# OpenMoteSTM-Border_JTAG.net
KiCad netlist of a schematic drawn in Altium Designer
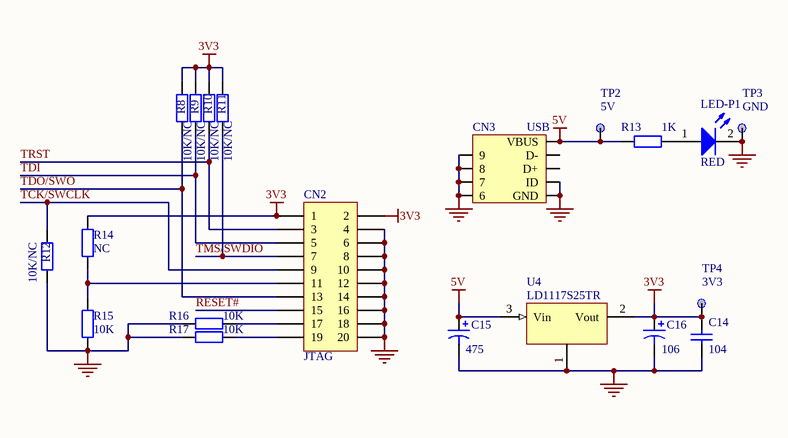
[diagram p0: OpenMoteSTM-Border_JTAG.SchDoc]

(export (version "E")
  (design (tool "Eeschema 10.0.6"))
  (components
    (comp (ref "C14")
      (value "104")
      (footprint "0603")
      (description "Capacitor")
      (fields (field (name "Comment") "Cap") (field (name "PUBLISHER") "Altium Limited"))
      (libsource (lib "Miscellaneous Devices") (part "Cap"))
    )
    (comp (ref "C15")
      (value "475")
      (footprint "1210")
      (description "Polarized Capacitor (Radial)")
      (fields (field (name "Comment") "Cap Pol1") (field (name "PUBLISHER") "Altium Limited"))
      (libsource (lib "Miscellaneous Devices") (part "Cap Pol1"))
    )
    (comp (ref "C16")
      (value "106")
      (footprint "1210")
      (description "Polarized Capacitor (Radial)")
      (fields (field (name "Comment") "Cap Pol1") (field (name "PUBLISHER") "Altium Limited"))
      (libsource (lib "Miscellaneous Devices") (part "Cap Pol1"))
    )
    (comp (ref "CN2")
      (value "JTAG")
      (footprint "HDR2X10")
      (description "Header, 10-Pin, Dual row")
      (fields (field (name "PUBLISHER") "Altium Limited"))
      (libsource (lib "Miscellaneous Connectors") (part "Header 10X2"))
    )
    (comp (ref "CN3")
      (value "USB")
      (footprint "MINI-USB")
      (libsource (lib "OpenMoteSTM-Border") (part "MINIUSB_A"))
    )
    (comp (ref "LED-P1")
      (value "RED")
      (footprint "0603")
      (description "Typical RED, GREEN, YELLOW, AMBER GaAs LED")
      (fields (field (name "PUBLISHER") "Altium Limited"))
      (libsource (lib "Miscellaneous Devices") (part "LED2"))
    )
    (comp (ref "R8")
      (value "10K/NC")
      (footprint "0603")
      (description "Resistor")
      (fields (field (name "Comment") "Res2") (field (name "PUBLISHER") "Altium Limited"))
      (libsource (lib "Miscellaneous Devices") (part "Res2"))
    )
    (comp (ref "R9")
      (value "10K/NC")
      (footprint "0603")
      (description "Resistor")
      (fields (field (name "Comment") "Res2") (field (name "PUBLISHER") "Altium Limited"))
      (libsource (lib "Miscellaneous Devices") (part "Res2"))
    )
    (comp (ref "R10")
      (value "10K/NC")
      (footprint "0603")
      (description "Resistor")
      (fields (field (name "Comment") "Res2") (field (name "PUBLISHER") "Altium Limited"))
      (libsource (lib "Miscellaneous Devices") (part "Res2"))
    )
    (comp (ref "R11")
      (value "10K/NC")
      (footprint "0603")
      (description "Resistor")
      (fields (field (name "Comment") "Res2") (field (name "PUBLISHER") "Altium Limited"))
      (libsource (lib "Miscellaneous Devices") (part "Res2"))
    )
    (comp (ref "R12")
      (value "10K/NC")
      (footprint "0603")
      (description "Resistor")
      (fields (field (name "Comment") "Res2") (field (name "PUBLISHER") "Altium Limited"))
      (libsource (lib "Miscellaneous Devices") (part "Res2"))
    )
    (comp (ref "R13")
      (value "1K")
      (footprint "0603")
      (description "Resistor")
      (fields (field (name "Comment") "Res2") (field (name "PUBLISHER") "Altium Limited"))
      (libsource (lib "") (part "Res2_1"))
    )
    (comp (ref "R14")
      (value "NC")
      (footprint "0603")
      (description "Resistor")
      (fields (field (name "Comment") "Res2") (field (name "PUBLISHER") "Altium Limited"))
      (libsource (lib "Miscellaneous Devices") (part "Res2"))
    )
    (comp (ref "R15")
      (value "10K")
      (footprint "0603")
      (description "Resistor")
      (fields (field (name "Comment") "Res2") (field (name "PUBLISHER") "Altium Limited"))
      (libsource (lib "Miscellaneous Devices") (part "Res2"))
    )
    (comp (ref "R16")
      (value "10K")
      (footprint "0603")
      (description "Resistor")
      (fields (field (name "Comment") "Res2") (field (name "PUBLISHER") "Altium Limited"))
      (libsource (lib "") (part "Res2_1"))
    )
    (comp (ref "R17")
      (value "10K")
      (footprint "0603")
      (description "Resistor")
      (fields (field (name "Comment") "Res2") (field (name "PUBLISHER") "Altium Limited"))
      (libsource (lib "") (part "Res2_1"))
    )
    (comp (ref "TP2") (value "5V") (footprint "TP") (libsource (lib "*") (part "TP")))
    (comp (ref "TP3") (value "GND") (footprint "TP") (libsource (lib "*") (part "TP")))
    (comp (ref "TP4") (value "3V3") (footprint "TP") (libsource (lib "*") (part "TP")))
    (comp (ref "U4") (value "LD1117S25TR") (footprint "LD1117") (libsource (lib "*") (part "LD1117")))
  )
  (nets
    (net (code "1") (name "/RESET#") (class "Default")
      (node (ref "CN2") (pin "15") (pinfunction "15_15") (pintype "passive"))
    )
    (net (code "2") (name "/TCK{slash}SWCLK") (class "Default")
      (node (ref "CN2") (pin "9") (pinfunction "9_9") (pintype "passive"))
      (node (ref "R12") (pin "2") (pinfunction "2_2") (pintype "passive"))
    )
    (net (code "3") (name "/TDI") (class "Default")
      (node (ref "CN2") (pin "5") (pinfunction "5_5") (pintype "passive"))
      (node (ref "R9") (pin "1") (pinfunction "1_1") (pintype "passive"))
    )
    (net (code "4") (name "/TDO{slash}SWO") (class "Default")
      (node (ref "CN2") (pin "13") (pinfunction "13_13") (pintype "passive"))
      (node (ref "R8") (pin "1") (pinfunction "1_1") (pintype "passive"))
    )
    (net (code "5") (name "/TMS{slash}SWDIO") (class "Default")
      (node (ref "CN2") (pin "7") (pinfunction "7_7") (pintype "passive"))
      (node (ref "R11") (pin "1") (pinfunction "1_1") (pintype "passive"))
    )
    (net (code "6") (name "/TRST") (class "Default")
      (node (ref "CN2") (pin "3") (pinfunction "3_3") (pintype "passive"))
      (node (ref "R10") (pin "1") (pinfunction "1_1") (pintype "passive"))
    )
    (net (code "7") (name "3V3") (class "Default")
      (node (ref "C14") (pin "2") (pinfunction "2_2") (pintype "passive"))
      (node (ref "C16") (pin "1") (pinfunction "1_1") (pintype "passive"))
      (node (ref "CN2") (pin "1") (pinfunction "1_1") (pintype "passive"))
      (node (ref "CN2") (pin "2") (pinfunction "2_2") (pintype "passive"))
      (node (ref "R10") (pin "2") (pinfunction "2_2") (pintype "passive"))
      (node (ref "R11") (pin "2") (pinfunction "2_2") (pintype "passive"))
      (node (ref "R14") (pin "2") (pinfunction "2_2") (pintype "passive"))
      (node (ref "R8") (pin "2") (pinfunction "2_2") (pintype "passive"))
      (node (ref "R9") (pin "2") (pinfunction "2_2") (pintype "passive"))
      (node (ref "TP4") (pin "1") (pinfunction "1_1") (pintype "passive"))
      (node (ref "U4") (pin "2") (pinfunction "Vout_2") (pintype "power_in"))
    )
    (net (code "8") (name "5V") (class "Default")
      (node (ref "C15") (pin "1") (pinfunction "1_1") (pintype "passive"))
      (node (ref "CN3") (pin "1") (pinfunction "VBUS_1") (pintype "passive"))
      (node (ref "R13") (pin "2") (pinfunction "2_2") (pintype "passive"))
      (node (ref "TP2") (pin "1") (pinfunction "1_1") (pintype "passive"))
      (node (ref "U4") (pin "3") (pinfunction "Vin_3") (pintype "input"))
    )
    (net (code "9") (name "GND") (class "Default")
      (node (ref "C14") (pin "1") (pinfunction "1_1") (pintype "passive"))
      (node (ref "C15") (pin "2") (pinfunction "2_2") (pintype "passive"))
      (node (ref "C16") (pin "2") (pinfunction "2_2") (pintype "passive"))
      (node (ref "CN2") (pin "10") (pinfunction "10_10") (pintype "passive"))
      (node (ref "CN2") (pin "12") (pinfunction "12_12") (pintype "passive"))
      (node (ref "CN2") (pin "14") (pinfunction "14_14") (pintype "passive"))
      (node (ref "CN2") (pin "16") (pinfunction "16_16") (pintype "passive"))
      (node (ref "CN2") (pin "18") (pinfunction "18_18") (pintype "passive"))
      (node (ref "CN2") (pin "20") (pinfunction "20_20") (pintype "passive"))
      (node (ref "CN2") (pin "4") (pinfunction "4_4") (pintype "passive"))
      (node (ref "CN2") (pin "6") (pinfunction "6_6") (pintype "passive"))
      (node (ref "CN2") (pin "8") (pinfunction "8_8") (pintype "passive"))
      (node (ref "CN3") (pin "4") (pinfunction "ID_4") (pintype "passive"))
      (node (ref "CN3") (pin "5") (pinfunction "GND_5") (pintype "passive"))
      (node (ref "CN3") (pin "6") (pinfunction "6_6") (pintype "passive"))
      (node (ref "CN3") (pin "7") (pinfunction "7_7") (pintype "passive"))
      (node (ref "CN3") (pin "8") (pinfunction "8_8") (pintype "passive"))
      (node (ref "CN3") (pin "9") (pinfunction "9_9") (pintype "passive"))
      (node (ref "LED-P1") (pin "2") (pinfunction "K_2") (pintype "passive"))
      (node (ref "R12") (pin "1") (pinfunction "1_1") (pintype "passive"))
      (node (ref "R15") (pin "1") (pinfunction "1_1") (pintype "passive"))
      (node (ref "R16") (pin "2") (pinfunction "2_2") (pintype "passive"))
      (node (ref "R17") (pin "2") (pinfunction "2_2") (pintype "passive"))
      (node (ref "TP3") (pin "1") (pinfunction "1_1") (pintype "passive"))
      (node (ref "U4") (pin "1") (pintype "passive"))
    )
    (net (code "10") (name "Net-(CN2-Pad11)") (class "Default")
      (node (ref "CN2") (pin "11") (pinfunction "11_11") (pintype "passive"))
      (node (ref "R14") (pin "1") (pinfunction "1_1") (pintype "passive"))
      (node (ref "R15") (pin "2") (pinfunction "2_2") (pintype "passive"))
    )
    (net (code "11") (name "Net-(CN2-Pad17)") (class "Default")
      (node (ref "CN2") (pin "17") (pinfunction "17_17") (pintype "passive"))
      (node (ref "R16") (pin "1") (pinfunction "1_1") (pintype "passive"))
    )
    (net (code "12") (name "Net-(CN2-Pad19)") (class "Default")
      (node (ref "CN2") (pin "19") (pinfunction "19_19") (pintype "passive"))
      (node (ref "R17") (pin "1") (pinfunction "1_1") (pintype "passive"))
    )
    (net (code "13") (name "Net-(LED-P1-A)") (class "Default")
      (node (ref "LED-P1") (pin "1") (pinfunction "A_1") (pintype "passive"))
      (node (ref "R13") (pin "1") (pinfunction "1_1") (pintype "passive"))
    )
    (net (code "14") (name "unconnected-(CN3-D+-Pad3)") (class "Default")
      (node (ref "CN3") (pin "3") (pinfunction "D+_3") (pintype "passive"))
    )
    (net (code "15") (name "unconnected-(CN3-D--Pad2)") (class "Default")
      (node (ref "CN3") (pin "2") (pinfunction "D-_2") (pintype "passive"))
    )
  )
)
